# Sync_Transformer.net
KiCad netlist of a schematic drawn in Altium Designer
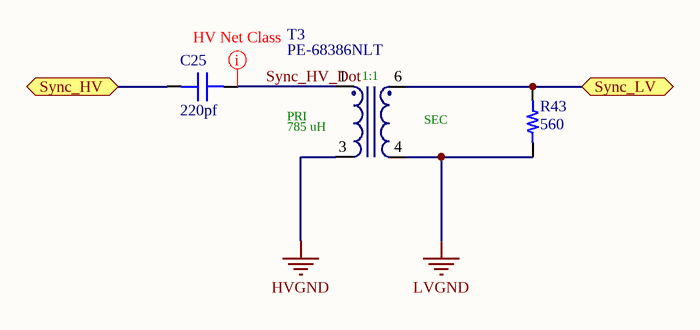
[diagram p0: Sync Transformer.SchDoc]

(export (version "E")
  (design (tool "Eeschema 10.0.6"))
  (components
    (comp (ref "C25")
      (value "220pf")
      (footprint "CAP 0603/1608")
      (fields
        (field (name "Comment") "Capacitor MLCC 220pf 25V CAP 0603/1608")
        (field (name "CREATED_BY") "Nick Mah")
      )
      (libsource (lib "Altium-Lib") (part "Capacitor"))
    )
    (comp (ref "R43")
      (value "560")
      (footprint "RES 0603/1608")
      (fields
        (field (name "TOLERANCE") "1%")
        (field (name "POWER") "1/10W")
        (field (name "Comment") "Resistor 560 0603 1/10W 1%")
        (field (name "CREATED_BY") "Nick Mah")
      )
      (libsource (lib "Altium-Lib") (part "Resistor"))
    )
    (comp (ref "T3")
      (value "Sync Transformer")
      (footprint "PE-68386NLT")
      (description "PULSE XFMR 1:1 785UH")
      (fields
        (field (name "MFRPARTNO") "PE-68386NLT")
        (field (name "COMPONENTLINK1URL") "file:///C:/Users/Nick%20Mah/Downloads/SPM2007_61.pdf")
        (field (name "CREATED_BY") "Nick Mah")
      )
      (libsource (lib "Altium-Lib") (part "PE-68386NLT"))
    )
  )
  (nets
    (net (code "1") (name "/Sync_HV") (class "Default")
      (node (ref "C25") (pin "1") (pinfunction "1_1") (pintype "passive"))
    )
    (net (code "2") (name "/Sync_HV_Dot") (class "Default")
      (node (ref "C25") (pin "2") (pinfunction "2_2") (pintype "passive"))
      (node (ref "T3") (pin "1") (pinfunction "1_1") (pintype "passive"))
    )
    (net (code "3") (name "/Sync_LV") (class "Default")
      (node (ref "R43") (pin "2") (pinfunction "2_2") (pintype "passive"))
      (node (ref "T3") (pin "6") (pinfunction "6_6") (pintype "passive"))
    )
    (net (code "4") (name "HVGND") (class "Default")
      (node (ref "T3") (pin "3") (pinfunction "3_3") (pintype "passive"))
    )
    (net (code "5") (name "LVGND") (class "Default")
      (node (ref "R43") (pin "1") (pinfunction "1_1") (pintype "passive"))
      (node (ref "T3") (pin "4") (pinfunction "4_4") (pintype "passive"))
    )
  )
)
